# OBD-UART.net
KiCad netlist of a schematic drawn in EAGLE
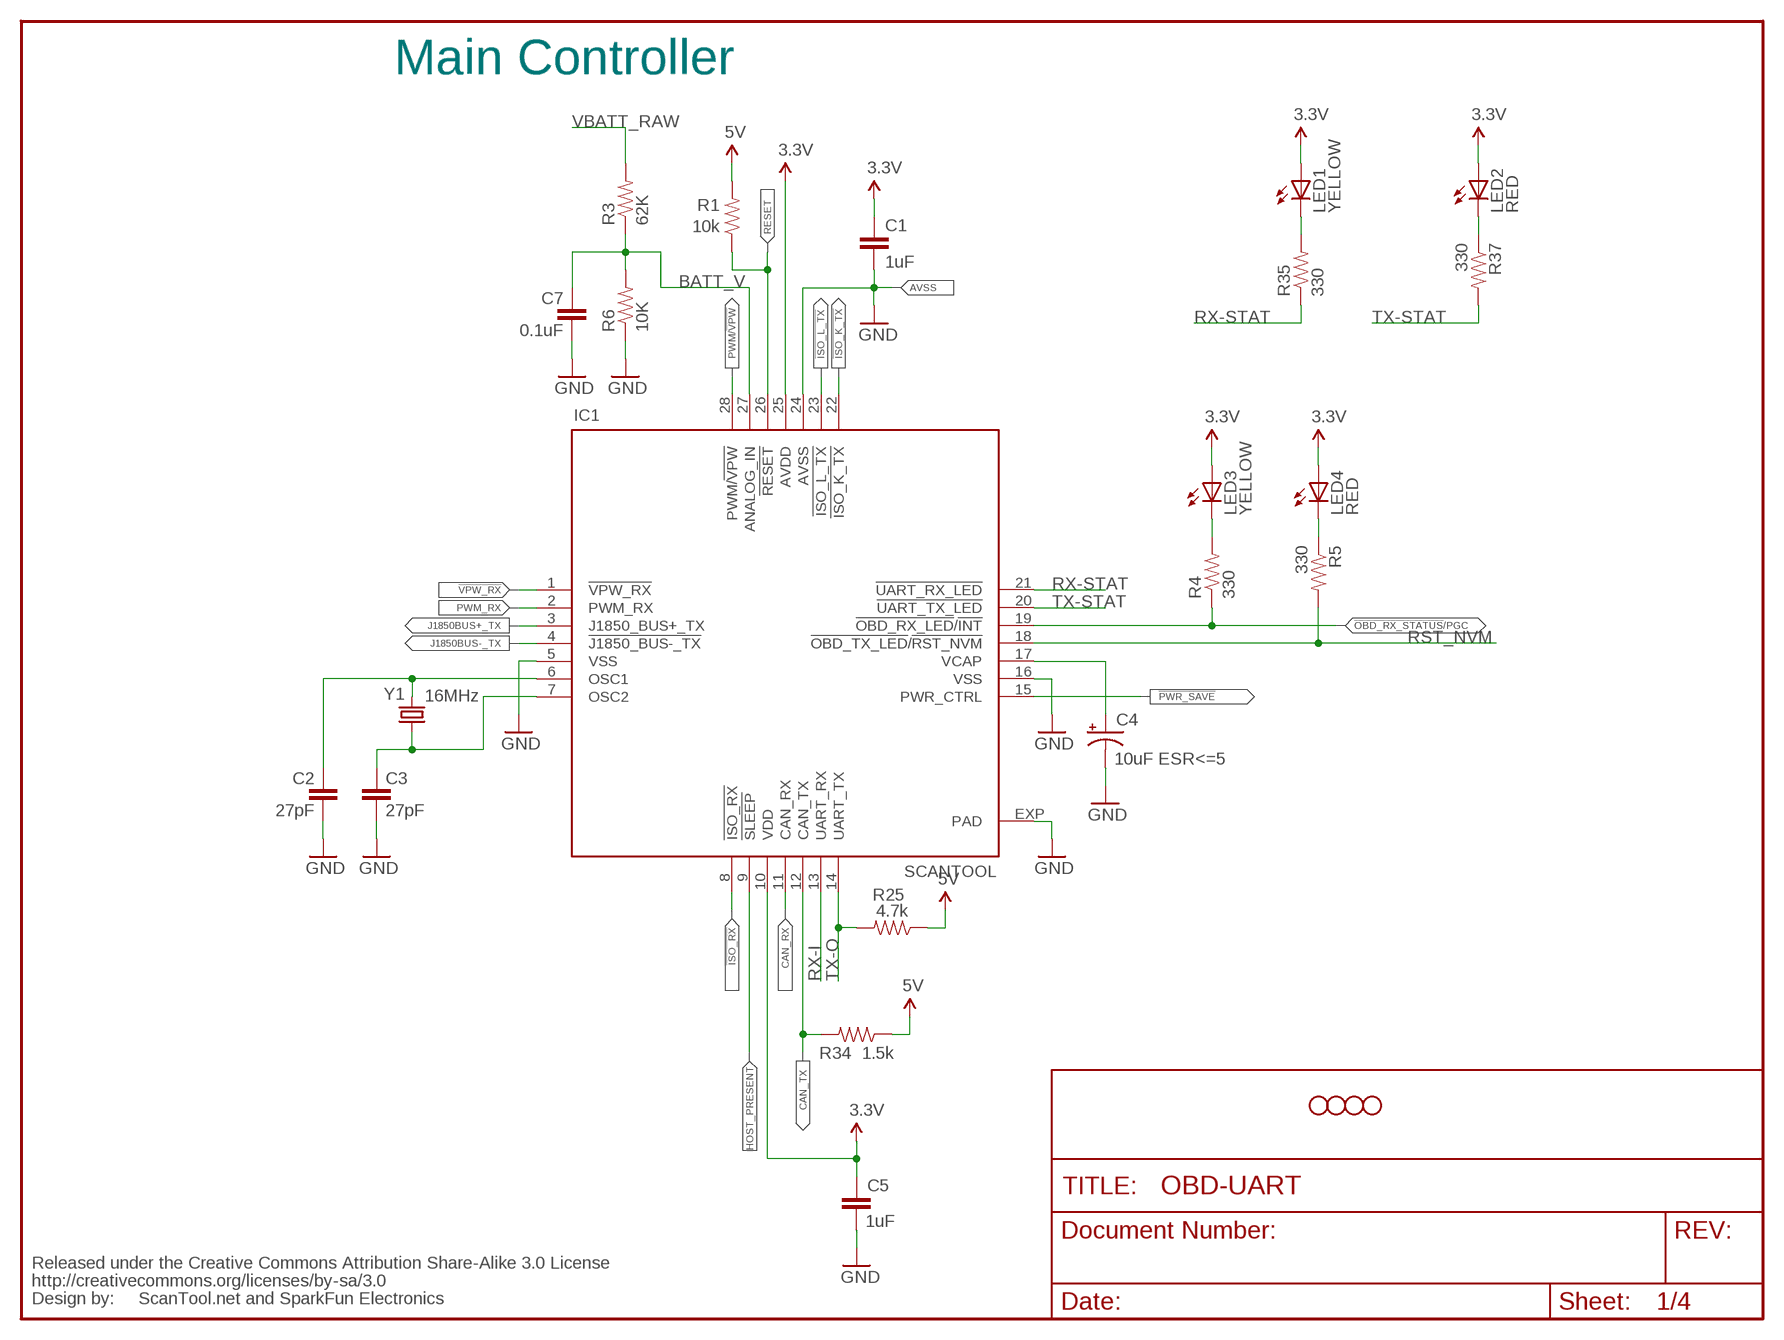
[diagram p0: schematic, sheet 1]
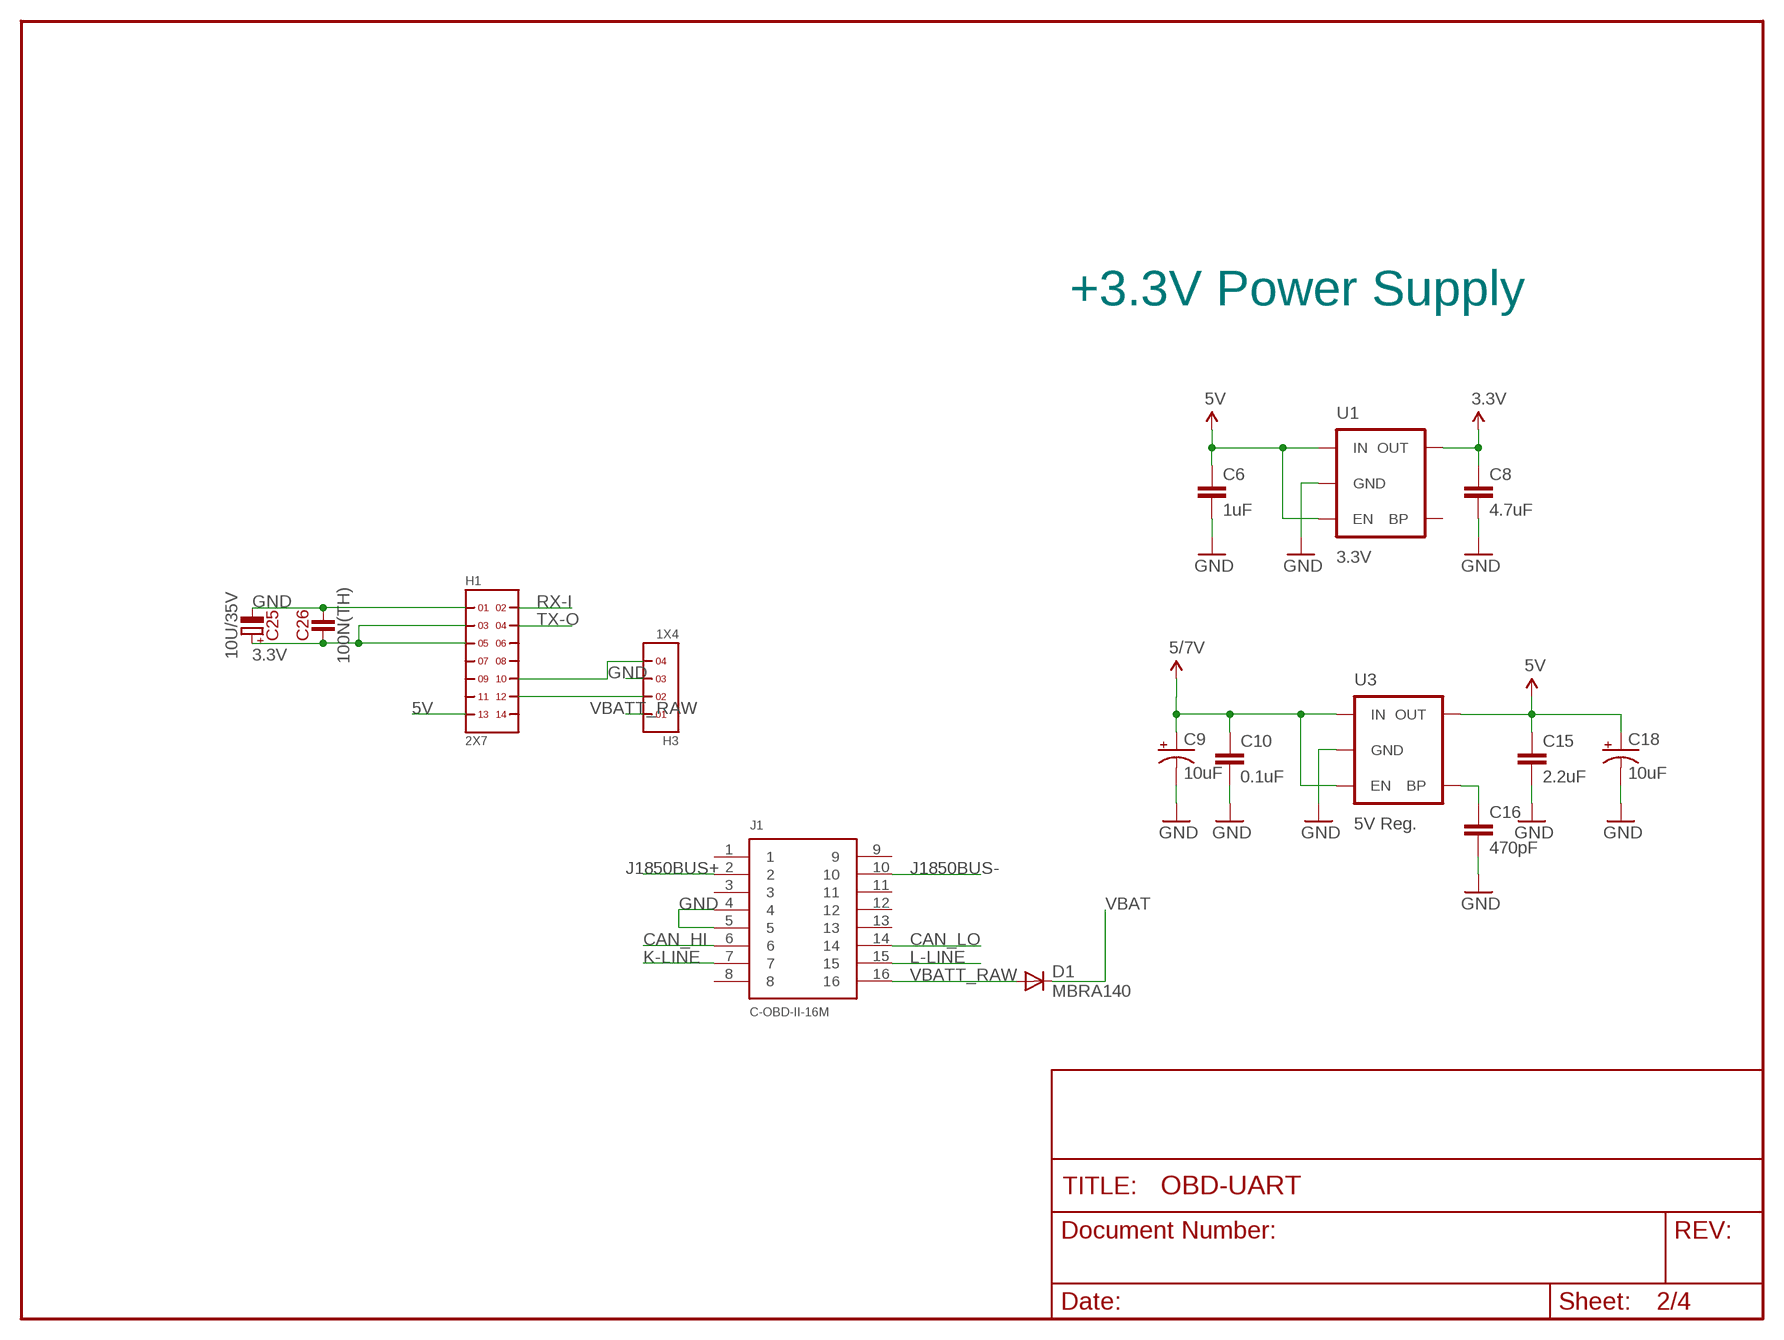
[diagram p1: schematic, sheet 2]
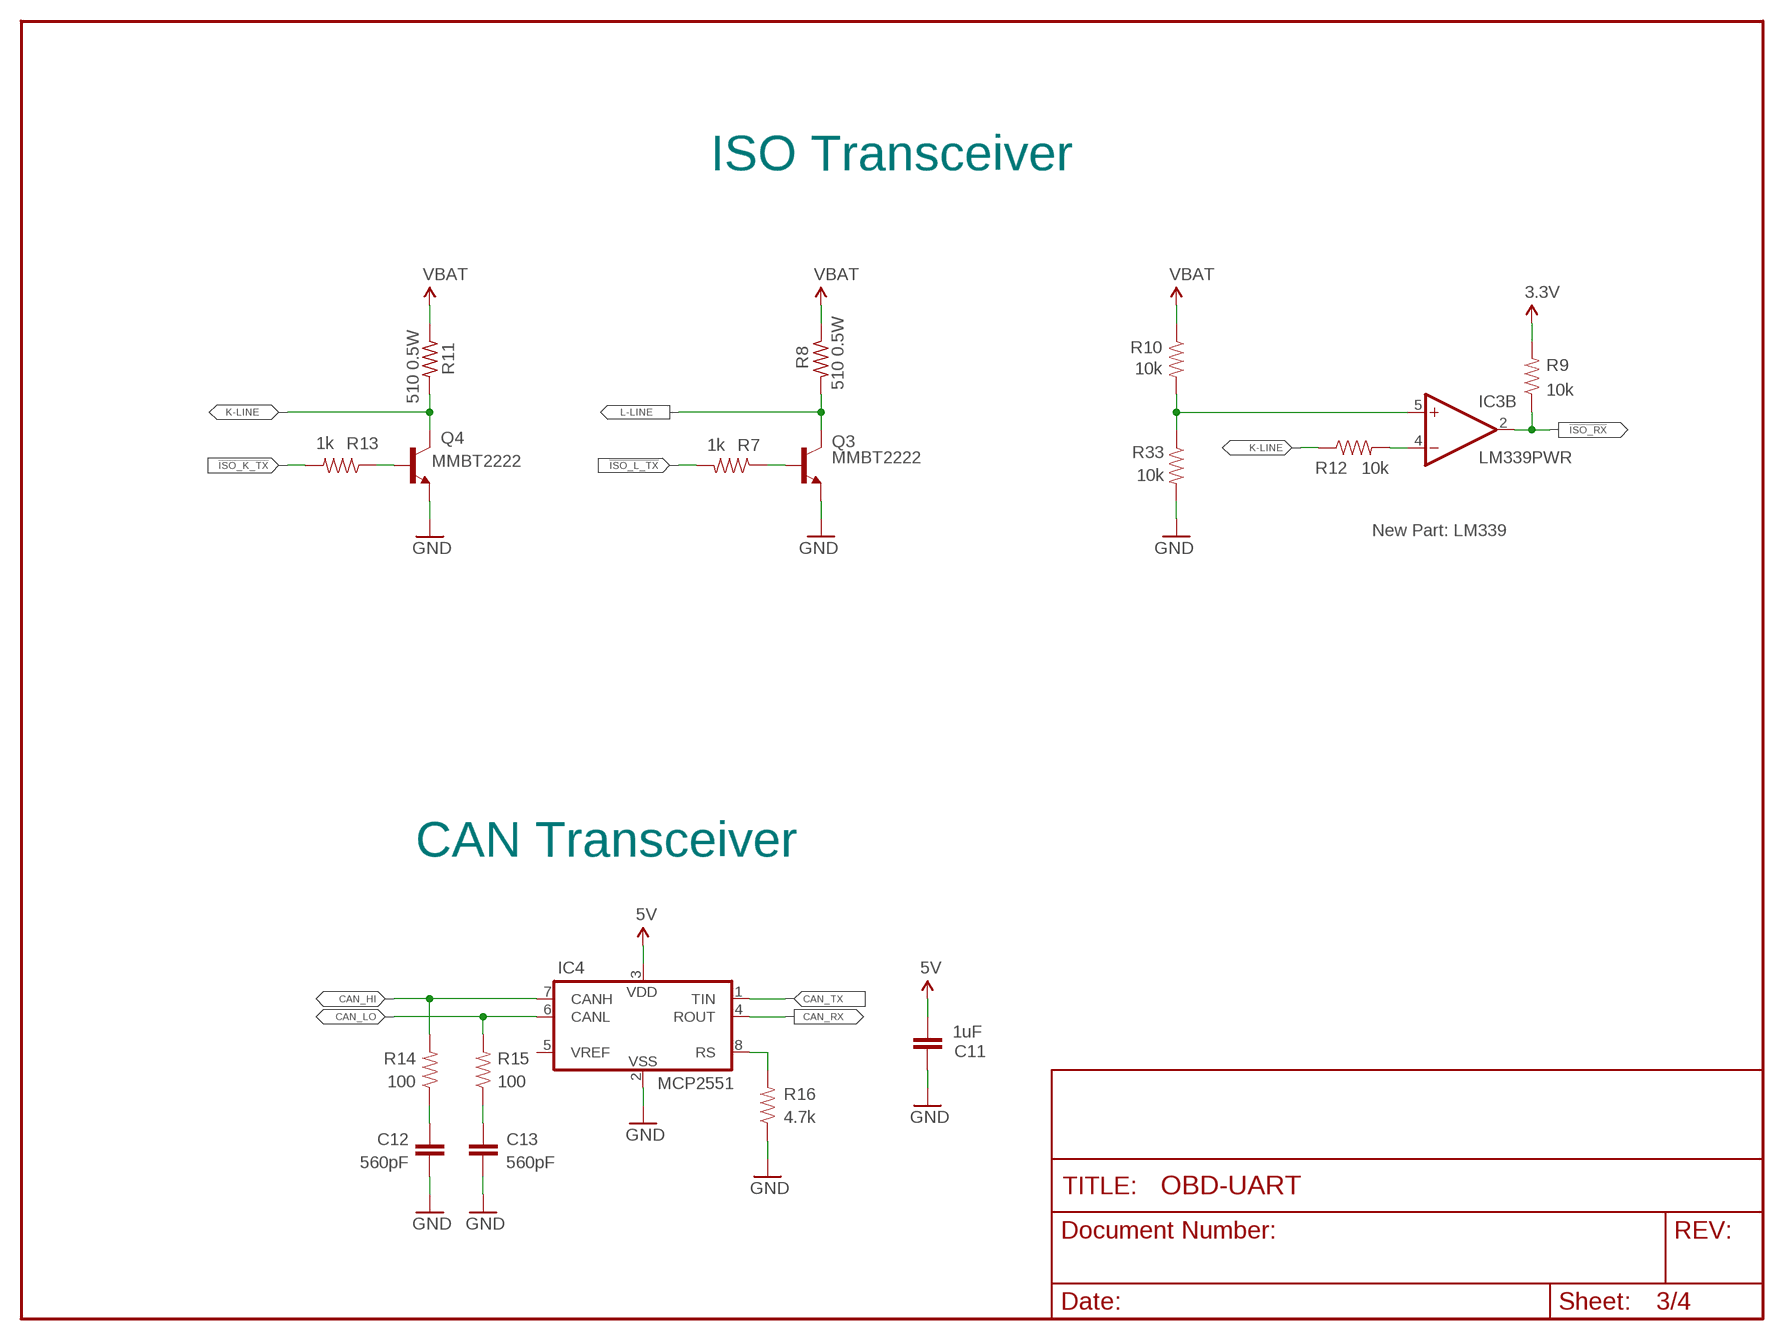
[diagram p2: schematic, sheet 3]
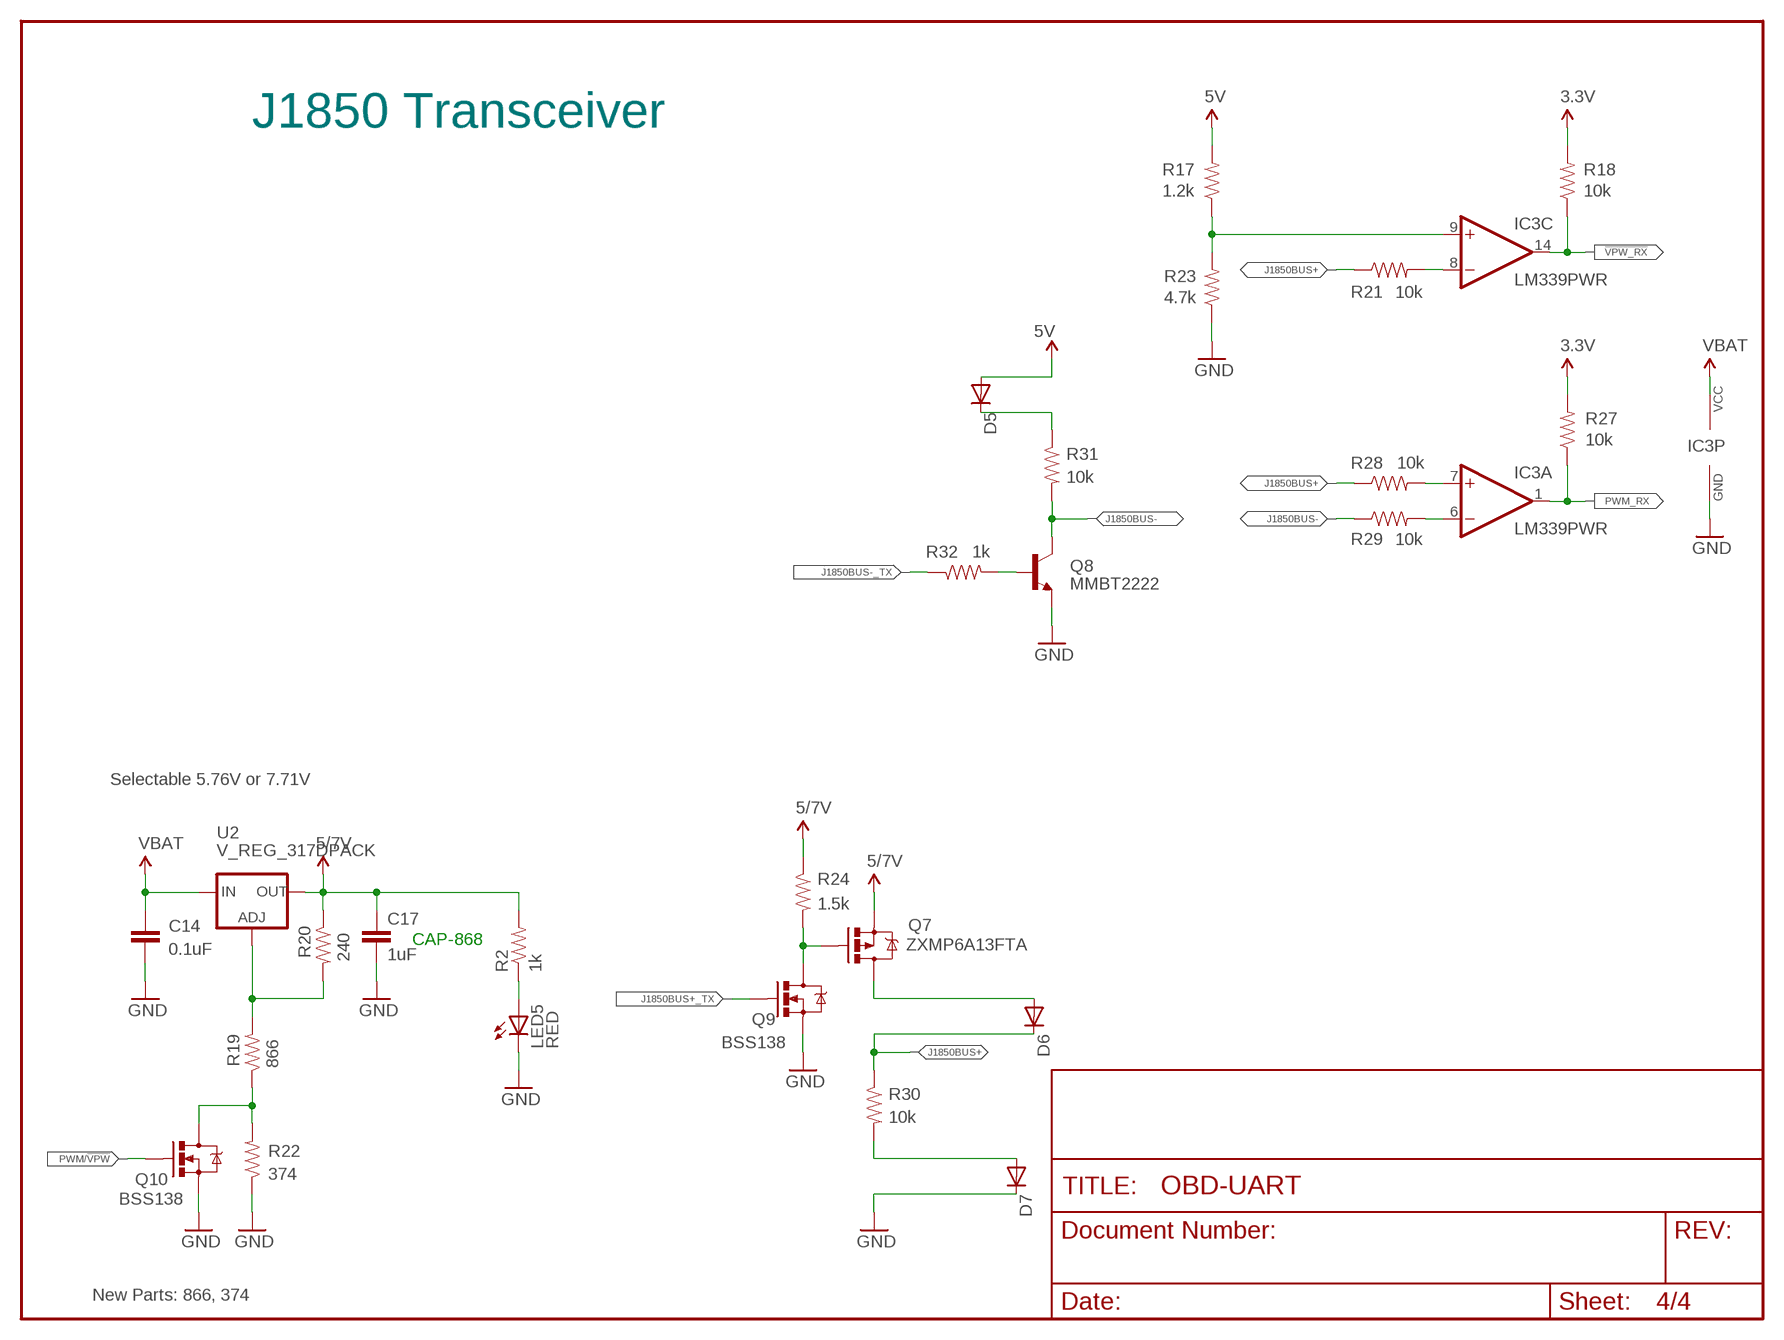
[diagram p3: schematic, sheet 4]

(export (version "E")
  (design (tool "Eeschema 10.0.6"))
  (components
    (comp (ref "C14")
      (value "0.1uF")
      (footprint "eagle-import:0402-CAP")
      (libsource (lib "eagle-import") (part "CAP0402-CAP"))
    )
    (comp (ref "C17")
      (value "1uF")
      (footprint "eagle-import:0402-CAP")
      (libsource (lib "eagle-import") (part "CAP0402-CAP"))
    )
    (comp (ref "D5")
      (value "DIODESOT23")
      (footprint "eagle-import:SOT23-3")
      (libsource (lib "eagle-import") (part "DIODESOT23"))
    )
    (comp (ref "D6")
      (value "DIODESOT23")
      (footprint "eagle-import:SOT23-3")
      (libsource (lib "eagle-import") (part "DIODESOT23"))
    )
    (comp (ref "D7")
      (value "DIODESOT23")
      (footprint "eagle-import:SOT23-3")
      (libsource (lib "eagle-import") (part "DIODESOT23"))
    )
    (comp (ref "IC3")
      (value "LM339PWR")
      (footprint "eagle-import:TSSOP-14")
      (libsource (lib "eagle-import") (part "LM339PWR"))
    )
    (comp (ref "LED5")
      (value "RED")
      (footprint "eagle-import:LED-0603")
      (libsource (lib "eagle-import") (part "LED0603"))
    )
    (comp (ref "Q7")
      (value "ZXMP6A13FTA")
      (footprint "eagle-import:SOT23")
      (libsource (lib "eagle-import") (part "MOSFET-PCHANNEL"))
    )
    (comp (ref "Q8")
      (value "MMBT2222")
      (footprint "eagle-import:SOT23-3")
      (libsource (lib "eagle-import") (part "TRANSISTOR_NPNSOT23-3"))
    )
    (comp (ref "Q9")
      (value "BSS138")
      (footprint "eagle-import:SOT23-3")
      (libsource (lib "eagle-import") (part "MOSFET-NCHANNELSMD"))
    )
    (comp (ref "Q10")
      (value "BSS138")
      (footprint "eagle-import:SOT23-3")
      (libsource (lib "eagle-import") (part "MOSFET-NCHANNELSMD"))
    )
    (comp (ref "R2")
      (value "1k")
      (footprint "eagle-import:0402-RES")
      (libsource (lib "eagle-import") (part "RESISTOR0402-RES"))
    )
    (comp (ref "R17")
      (value "1.2k")
      (footprint "eagle-import:0402-RES")
      (libsource (lib "eagle-import") (part "RESISTOR0402-RES"))
    )
    (comp (ref "R18")
      (value "10k")
      (footprint "eagle-import:0402-RES")
      (libsource (lib "eagle-import") (part "RESISTOR0402-RES"))
    )
    (comp (ref "R19")
      (value "866")
      (footprint "eagle-import:0402-RES")
      (libsource (lib "eagle-import") (part "RESISTOR0402-RES"))
    )
    (comp (ref "R20")
      (value "240")
      (footprint "eagle-import:0402-RES")
      (libsource (lib "eagle-import") (part "RESISTOR0402-RES"))
    )
    (comp (ref "R21")
      (value "10k")
      (footprint "eagle-import:0402-RES")
      (libsource (lib "eagle-import") (part "RESISTOR0402-RES"))
    )
    (comp (ref "R22")
      (value "374")
      (footprint "eagle-import:0402-RES")
      (libsource (lib "eagle-import") (part "RESISTOR0402-RES"))
    )
    (comp (ref "R23")
      (value "4.7k")
      (footprint "eagle-import:0402-RES")
      (libsource (lib "eagle-import") (part "RESISTOR0402-RES"))
    )
    (comp (ref "R24")
      (value "1.5k")
      (footprint "eagle-import:0402-RES")
      (libsource (lib "eagle-import") (part "RESISTOR0402-RES"))
    )
    (comp (ref "R27")
      (value "10k")
      (footprint "eagle-import:0402-RES")
      (libsource (lib "eagle-import") (part "RESISTOR0402-RES"))
    )
    (comp (ref "R28")
      (value "10k")
      (footprint "eagle-import:0402-RES")
      (libsource (lib "eagle-import") (part "RESISTOR0402-RES"))
    )
    (comp (ref "R29")
      (value "10k")
      (footprint "eagle-import:0402-RES")
      (libsource (lib "eagle-import") (part "RESISTOR0402-RES"))
    )
    (comp (ref "R30")
      (value "10k")
      (footprint "eagle-import:0402-RES")
      (libsource (lib "eagle-import") (part "RESISTOR0402-RES"))
    )
    (comp (ref "R31")
      (value "10k")
      (footprint "eagle-import:0402-RES")
      (libsource (lib "eagle-import") (part "RESISTOR0402-RES"))
    )
    (comp (ref "R32")
      (value "1k")
      (footprint "eagle-import:0402-RES")
      (libsource (lib "eagle-import") (part "RESISTOR0402-RES"))
    )
    (comp (ref "U2")
      (value "V_REG_317DPACK")
      (footprint "eagle-import:V-REG_DPACK")
      (libsource (lib "eagle-import") (part "V_REG_317DPACK"))
    )
    (comp (ref "C1")
      (value "1uF")
      (footprint "eagle-import:0402-CAP")
      (libsource (lib "eagle-import") (part "CAP0402-CAP"))
    )
    (comp (ref "C2")
      (value "27pF")
      (footprint "eagle-import:0402-CAP")
      (libsource (lib "eagle-import") (part "CAP0402-CAP"))
    )
    (comp (ref "C3")
      (value "27pF")
      (footprint "eagle-import:0402-CAP")
      (libsource (lib "eagle-import") (part "CAP0402-CAP"))
    )
    (comp (ref "C4")
      (value "10uF ESR<=5")
      (footprint "eagle-import:EIA3216")
      (libsource (lib "eagle-import") (part "CAP_POL1206"))
    )
    (comp (ref "C5")
      (value "1uF")
      (footprint "eagle-import:0402-CAP")
      (libsource (lib "eagle-import") (part "CAP0402-CAP"))
    )
    (comp (ref "C7")
      (value "0.1uF")
      (footprint "eagle-import:0402-CAP")
      (libsource (lib "eagle-import") (part "CAP0402-CAP"))
    )
    (comp (ref "IC1")
      (value "SCANTOOL")
      (footprint "eagle-import:_STN_SCANTOOL_QFN-28-S")
      (libsource (lib "eagle-import") (part "SCANTOOL"))
    )
    (comp (ref "JP4")
      (value "STAND-OFF")
      (footprint "eagle-import:STAND-OFF")
      (libsource (lib "eagle-import") (part "STAND-OFF"))
    )
    (comp (ref "JP5")
      (value "STAND-OFF")
      (footprint "eagle-import:STAND-OFF")
      (libsource (lib "eagle-import") (part "STAND-OFF"))
    )
    (comp (ref "JP6")
      (value "STAND-OFF")
      (footprint "eagle-import:STAND-OFF")
      (libsource (lib "eagle-import") (part "STAND-OFF"))
    )
    (comp (ref "JP7")
      (value "STAND-OFF")
      (footprint "eagle-import:STAND-OFF")
      (libsource (lib "eagle-import") (part "STAND-OFF"))
    )
    (comp (ref "LED1")
      (value "YELLOW")
      (footprint "eagle-import:LED-0603")
      (libsource (lib "eagle-import") (part "LED0603"))
    )
    (comp (ref "LED2")
      (value "RED")
      (footprint "eagle-import:LED-0603")
      (libsource (lib "eagle-import") (part "LED0603"))
    )
    (comp (ref "LED3")
      (value "YELLOW")
      (footprint "eagle-import:LED-0603")
      (libsource (lib "eagle-import") (part "LED0603"))
    )
    (comp (ref "LED4")
      (value "RED")
      (footprint "eagle-import:LED-0603")
      (libsource (lib "eagle-import") (part "LED0603"))
    )
    (comp (ref "R1")
      (value "10k")
      (footprint "eagle-import:0402-RES")
      (libsource (lib "eagle-import") (part "RESISTOR0402-RES"))
    )
    (comp (ref "R3")
      (value "62K")
      (footprint "eagle-import:0402-RES")
      (libsource (lib "eagle-import") (part "RESISTOR0402-RES"))
    )
    (comp (ref "R4")
      (value "330")
      (footprint "eagle-import:0402-RES")
      (libsource (lib "eagle-import") (part "RESISTOR0402-RES"))
    )
    (comp (ref "R5")
      (value "330")
      (footprint "eagle-import:0402-RES")
      (libsource (lib "eagle-import") (part "RESISTOR0402-RES"))
    )
    (comp (ref "R6")
      (value "10K")
      (footprint "eagle-import:0402-RES")
      (libsource (lib "eagle-import") (part "RESISTOR0402-RES"))
    )
    (comp (ref "R25")
      (value "4.7k")
      (footprint "eagle-import:0402-RES")
      (libsource (lib "eagle-import") (part "RESISTOR0402-RES"))
    )
    (comp (ref "R34")
      (value "1.5k")
      (footprint "eagle-import:0402-RES")
      (libsource (lib "eagle-import") (part "RESISTOR0402-RES"))
    )
    (comp (ref "R35")
      (value "330")
      (footprint "eagle-import:0402-RES")
      (libsource (lib "eagle-import") (part "RESISTOR0402-RES"))
    )
    (comp (ref "R37")
      (value "330")
      (footprint "eagle-import:0402-RES")
      (libsource (lib "eagle-import") (part "RESISTOR0402-RES"))
    )
    (comp (ref "U$1")
      (value "CREATIVE_COMMONS")
      (footprint "eagle-import:CREATIVE_COMMONS")
      (libsource (lib "eagle-import") (part "CREATIVE_COMMONS"))
    )
    (comp (ref "Y1")
      (value "16MHz")
      (footprint "eagle-import:CRYSTAL-SMD-5X3")
      (libsource (lib "eagle-import") (part "CRYSTAL5X3"))
    )
    (comp (ref "C11")
      (value "1uF")
      (footprint "eagle-import:0402-CAP")
      (libsource (lib "eagle-import") (part "CAP0402-CAP"))
    )
    (comp (ref "C12")
      (value "560pF")
      (footprint "eagle-import:0402-CAP")
      (libsource (lib "eagle-import") (part "CAP0402-CAP"))
    )
    (comp (ref "C13")
      (value "560pF")
      (footprint "eagle-import:0402-CAP")
      (libsource (lib "eagle-import") (part "CAP0402-CAP"))
    )
    (comp (ref "IC4")
      (value "MCP2551")
      (footprint "eagle-import:SO-8")
      (fields (field (name "PARTNUM") "MCP2551-I/SN"))
      (libsource (lib "eagle-import") (part "MCP2551-I/SN"))
    )
    (comp (ref "Q3")
      (value "MMBT2222")
      (footprint "eagle-import:SOT23-3")
      (libsource (lib "eagle-import") (part "TRANSISTOR_NPNSOT23-3"))
    )
    (comp (ref "Q4")
      (value "MMBT2222")
      (footprint "eagle-import:SOT23-3")
      (libsource (lib "eagle-import") (part "TRANSISTOR_NPNSOT23-3"))
    )
    (comp (ref "R7")
      (value "1k")
      (footprint "eagle-import:0402-RES")
      (libsource (lib "eagle-import") (part "RESISTOR0402-RES"))
    )
    (comp (ref "R8")
      (value "510 0.5W")
      (footprint "eagle-import:2010")
      (libsource (lib "eagle-import") (part "R-US_2010"))
    )
    (comp (ref "R9")
      (value "10k")
      (footprint "eagle-import:0402-RES")
      (libsource (lib "eagle-import") (part "RESISTOR0402-RES"))
    )
    (comp (ref "R10")
      (value "10k")
      (footprint "eagle-import:0402-RES")
      (libsource (lib "eagle-import") (part "RESISTOR0402-RES"))
    )
    (comp (ref "R11")
      (value "510 0.5W")
      (footprint "eagle-import:2010")
      (libsource (lib "eagle-import") (part "R-US_2010"))
    )
    (comp (ref "R12")
      (value "10k")
      (footprint "eagle-import:0402-RES")
      (libsource (lib "eagle-import") (part "RESISTOR0402-RES"))
    )
    (comp (ref "R13")
      (value "1k")
      (footprint "eagle-import:0402-RES")
      (libsource (lib "eagle-import") (part "RESISTOR0402-RES"))
    )
    (comp (ref "R14")
      (value "100")
      (footprint "eagle-import:0402-RES")
      (libsource (lib "eagle-import") (part "RESISTOR0402-RES"))
    )
    (comp (ref "R15")
      (value "100")
      (footprint "eagle-import:0402-RES")
      (libsource (lib "eagle-import") (part "RESISTOR0402-RES"))
    )
    (comp (ref "R16")
      (value "4.7k")
      (footprint "eagle-import:0402-RES")
      (libsource (lib "eagle-import") (part "RESISTOR0402-RES"))
    )
    (comp (ref "R33")
      (value "10k")
      (footprint "eagle-import:0402-RES")
      (libsource (lib "eagle-import") (part "RESISTOR0402-RES"))
    )
    (comp (ref "C6")
      (value "1uF")
      (footprint "eagle-import:0402-CAP")
      (libsource (lib "eagle-import") (part "CAP0402-CAP"))
    )
    (comp (ref "C8")
      (value "4.7uF")
      (footprint "eagle-import:0402-CAP")
      (libsource (lib "eagle-import") (part "CAP0402-CAP"))
    )
    (comp (ref "C9")
      (value "10uF")
      (footprint "eagle-import:EIA3216")
      (libsource (lib "eagle-import") (part "CAP_POL1206"))
    )
    (comp (ref "C10")
      (value "0.1uF")
      (footprint "eagle-import:0402-CAP")
      (libsource (lib "eagle-import") (part "CAP0402-CAP"))
    )
    (comp (ref "C15")
      (value "2.2uF")
      (footprint "eagle-import:0402-CAP")
      (libsource (lib "eagle-import") (part "CAP0402-CAP"))
    )
    (comp (ref "C16")
      (value "470pF")
      (footprint "eagle-import:0402-CAP")
      (libsource (lib "eagle-import") (part "CAP0402-CAP"))
    )
    (comp (ref "C18")
      (value "10uF")
      (footprint "eagle-import:EIA3216")
      (libsource (lib "eagle-import") (part "CAP_POL1206"))
    )
    (comp (ref "C25")
      (value "10U/35V")
      (footprint "eagle-import:E2-5")
      (libsource (lib "eagle-import") (part "?10U/35V"))
    )
    (comp (ref "C26")
      (value "100N(TH)")
      (footprint "eagle-import:C050-024X044")
      (libsource (lib "eagle-import") (part "?100N(TH)"))
    )
    (comp (ref "D1")
      (value "MBRA140")
      (footprint "eagle-import:SMA-DIODE")
      (libsource (lib "eagle-import") (part "DIODESMA"))
    )
    (comp (ref "H1")
      (value "2X7")
      (footprint "eagle-import:2X7")
      (libsource (lib "eagle-import") (part "2X7"))
    )
    (comp (ref "H3")
      (value "1X4")
      (footprint "eagle-import:1X4")
      (libsource (lib "eagle-import") (part "1X4"))
    )
    (comp (ref "J1")
      (value "C-OBD-II-16M")
      (footprint "eagle-import:COMTECH_C-OBD-II-16M")
      (fields (field (name "MF") "Comtech Electronic Co., LTD"))
      (libsource (lib "eagle-import") (part "C-OBD-II-16M"))
    )
    (comp (ref "U1")
      (value "3.3V")
      (footprint "eagle-import:SOT23-5")
      (libsource (lib "eagle-import") (part "V_REG_LDOSMD"))
    )
    (comp (ref "U3")
      (value "5V Reg.")
      (footprint "eagle-import:SOT23-5")
      (libsource (lib "eagle-import") (part "V_REG_LDOSMD"))
    )
  )
  (nets
    (net (code "1") (name "3.3V") (class "Default")
      (node (ref "C1") (pin "1") (pinfunction "1_1") (pintype "passive"))
      (node (ref "C25") (pin "+") (pinfunction "+_+") (pintype "passive"))
      (node (ref "C26") (pin "1") (pinfunction "1_1") (pintype "passive"))
      (node (ref "C5") (pin "1") (pinfunction "1_1") (pintype "passive"))
      (node (ref "C8") (pin "1") (pinfunction "1_1") (pintype "passive"))
      (node (ref "H1") (pin "3") (pinfunction "3_3") (pintype "bidirectional"))
      (node (ref "H1") (pin "5") (pinfunction "5_5") (pintype "bidirectional"))
      (node (ref "IC1") (pin "10") (pinfunction "VDD_10") (pintype "power_in"))
      (node (ref "IC1") (pin "25") (pinfunction "AVDD_25") (pintype "power_in"))
      (node (ref "LED1") (pin "A") (pinfunction "A_A") (pintype "passive"))
      (node (ref "LED2") (pin "A") (pinfunction "A_A") (pintype "passive"))
      (node (ref "LED3") (pin "A") (pinfunction "A_A") (pintype "passive"))
      (node (ref "LED4") (pin "A") (pinfunction "A_A") (pintype "passive"))
      (node (ref "R18") (pin "2") (pinfunction "2_2") (pintype "passive"))
      (node (ref "R27") (pin "2") (pinfunction "2_2") (pintype "passive"))
      (node (ref "R9") (pin "2") (pinfunction "2_2") (pintype "passive"))
      (node (ref "U1") (pin "5") (pinfunction "OUT_5") (pintype "passive"))
    )
    (net (code "2") (name "5V") (class "Default")
      (node (ref "C11") (pin "1") (pinfunction "1_1") (pintype "passive"))
      (node (ref "C15") (pin "1") (pinfunction "1_1") (pintype "passive"))
      (node (ref "C18") (pin "A") (pinfunction "+_A") (pintype "passive"))
      (node (ref "C6") (pin "1") (pinfunction "1_1") (pintype "passive"))
      (node (ref "D5") (pin "1") (pinfunction "A_1") (pintype "passive"))
      (node (ref "H1") (pin "13") (pinfunction "13_13") (pintype "bidirectional"))
      (node (ref "IC4") (pin "3") (pinfunction "VDD_3") (pintype "power_in"))
      (node (ref "R1") (pin "2") (pinfunction "2_2") (pintype "passive"))
      (node (ref "R17") (pin "2") (pinfunction "2_2") (pintype "passive"))
      (node (ref "R25") (pin "1") (pinfunction "1_1") (pintype "passive"))
      (node (ref "R34") (pin "1") (pinfunction "1_1") (pintype "passive"))
      (node (ref "U1") (pin "1") (pinfunction "IN_1") (pintype "input"))
      (node (ref "U1") (pin "3") (pinfunction "EN_3") (pintype "input"))
      (node (ref "U3") (pin "5") (pinfunction "OUT_5") (pintype "passive"))
    )
    (net (code "3") (name "BATT_V") (class "Default")
      (node (ref "C7") (pin "1") (pinfunction "1_1") (pintype "passive"))
      (node (ref "IC1") (pin "27") (pinfunction "ANALOG_IN_27") (pintype "input"))
      (node (ref "R3") (pin "1") (pinfunction "1_1") (pintype "passive"))
      (node (ref "R6") (pin "2") (pinfunction "2_2") (pintype "passive"))
    )
    (net (code "4") (name "CAN_HI") (class "Default")
      (node (ref "IC4") (pin "7") (pinfunction "CANH_7") (pintype "bidirectional"))
      (node (ref "J1") (pin "6") (pinfunction "6_6") (pintype "passive"))
      (node (ref "R14") (pin "2") (pinfunction "2_2") (pintype "passive"))
    )
    (net (code "5") (name "CAN_LO") (class "Default")
      (node (ref "IC4") (pin "6") (pinfunction "CANL_6") (pintype "bidirectional"))
      (node (ref "J1") (pin "14") (pinfunction "14_14") (pintype "passive"))
      (node (ref "R15") (pin "2") (pinfunction "2_2") (pintype "passive"))
    )
    (net (code "6") (name "CAN_RX") (class "Default")
      (node (ref "IC1") (pin "11") (pinfunction "CAN_RX_11") (pintype "input"))
      (node (ref "IC4") (pin "4") (pinfunction "ROUT_4") (pintype "output"))
    )
    (net (code "7") (name "CAN_TX") (class "Default")
      (node (ref "IC1") (pin "12") (pinfunction "CAN_TX_12") (pintype "output"))
      (node (ref "IC4") (pin "1") (pinfunction "TIN_1") (pintype "input"))
      (node (ref "R34") (pin "2") (pinfunction "2_2") (pintype "passive"))
    )
    (net (code "8") (name "GND") (class "Default")
      (node (ref "C1") (pin "2") (pinfunction "2_2") (pintype "passive"))
      (node (ref "C10") (pin "2") (pinfunction "2_2") (pintype "passive"))
      (node (ref "C11") (pin "2") (pinfunction "2_2") (pintype "passive"))
      (node (ref "C12") (pin "2") (pinfunction "2_2") (pintype "passive"))
      (node (ref "C13") (pin "2") (pinfunction "2_2") (pintype "passive"))
      (node (ref "C14") (pin "2") (pinfunction "2_2") (pintype "passive"))
      (node (ref "C15") (pin "2") (pinfunction "2_2") (pintype "passive"))
      (node (ref "C16") (pin "2") (pinfunction "2_2") (pintype "passive"))
      (node (ref "C17") (pin "2") (pinfunction "2_2") (pintype "passive"))
      (node (ref "C18") (pin "C") (pinfunction "-_C") (pintype "passive"))
      (node (ref "C2") (pin "2") (pinfunction "2_2") (pintype "passive"))
      (node (ref "C25") (pin "-") (pinfunction "-_-") (pintype "passive"))
      (node (ref "C26") (pin "2") (pinfunction "2_2") (pintype "passive"))
      (node (ref "C3") (pin "2") (pinfunction "2_2") (pintype "passive"))
      (node (ref "C4") (pin "C") (pinfunction "-_C") (pintype "passive"))
      (node (ref "C5") (pin "2") (pinfunction "2_2") (pintype "passive"))
      (node (ref "C6") (pin "2") (pinfunction "2_2") (pintype "passive"))
      (node (ref "C7") (pin "2") (pinfunction "2_2") (pintype "passive"))
      (node (ref "C8") (pin "2") (pinfunction "2_2") (pintype "passive"))
      (node (ref "C9") (pin "C") (pinfunction "-_C") (pintype "passive"))
      (node (ref "D7") (pin "3") (pinfunction "C_3") (pintype "passive"))
      (node (ref "H1") (pin "1") (pinfunction "1_1") (pintype "bidirectional"))
      (node (ref "H3") (pin "3") (pinfunction "3_3") (pintype "bidirectional"))
      (node (ref "IC1") (pin "16") (pinfunction "VSS_16") (pintype "power_in"))
      (node (ref "IC1") (pin "24") (pinfunction "AVSS_24") (pintype "power_in"))
      (node (ref "IC1") (pin "5") (pinfunction "VSS_5") (pintype "power_in"))
      (node (ref "IC1") (pin "EXP") (pinfunction "PAD_EXP") (pintype "passive"))
      (node (ref "IC3") (pin "12") (pinfunction "GND_12") (pintype "power_in"))
      (node (ref "IC4") (pin "2") (pinfunction "VSS_2") (pintype "power_in"))
      (node (ref "J1") (pin "4") (pinfunction "4_4") (pintype "passive"))
      (node (ref "J1") (pin "5") (pinfunction "5_5") (pintype "passive"))
      (node (ref "LED5") (pin "C") (pinfunction "C_C") (pintype "passive"))
      (node (ref "Q10") (pin "2") (pinfunction "S_2") (pintype "passive"))
      (node (ref "Q3") (pin "2") (pinfunction "E_2") (pintype "passive"))
      (node (ref "Q4") (pin "2") (pinfunction "E_2") (pintype "passive"))
      (node (ref "Q8") (pin "2") (pinfunction "E_2") (pintype "passive"))
      (node (ref "Q9") (pin "2") (pinfunction "S_2") (pintype "passive"))
      (node (ref "R16") (pin "1") (pinfunction "1_1") (pintype "passive"))
      (node (ref "R22") (pin "1") (pinfunction "1_1") (pintype "passive"))
      (node (ref "R23") (pin "1") (pinfunction "1_1") (pintype "passive"))
      (node (ref "R33") (pin "2") (pinfunction "2_2") (pintype "passive"))
      (node (ref "R6") (pin "1") (pinfunction "1_1") (pintype "passive"))
      (node (ref "U1") (pin "2") (pinfunction "GND_2") (pintype "input"))
      (node (ref "U3") (pin "2") (pinfunction "GND_2") (pintype "input"))
    )
    (net (code "9") (name "HOST_PRESENT") (class "Default")
      (node (ref "IC1") (pin "9") (pinfunction "~{SLEEP}_9") (pintype "input"))
    )
    (net (code "10") (name "J1850BUS+") (class "Default")
      (node (ref "D6") (pin "3") (pinfunction "C_3") (pintype "passive"))
      (node (ref "J1") (pin "2") (pinfunction "2_2") (pintype "passive"))
      (node (ref "R21") (pin "1") (pinfunction "1_1") (pintype "passive"))
      (node (ref "R28") (pin "1") (pinfunction "1_1") (pintype "passive"))
      (node (ref "R30") (pin "1") (pinfunction "1_1") (pintype "passive"))
    )
    (net (code "11") (name "J1850BUS+_TX") (class "Default")
      (node (ref "IC1") (pin "3") (pinfunction "J1850_BUS+_TX_3") (pintype "output"))
      (node (ref "Q9") (pin "1") (pinfunction "G_1") (pintype "passive"))
    )
    (net (code "12") (name "J1850BUS-") (class "Default")
      (node (ref "J1") (pin "10") (pinfunction "10_10") (pintype "passive"))
      (node (ref "Q8") (pin "3") (pinfunction "C_3") (pintype "passive"))
      (node (ref "R29") (pin "1") (pinfunction "1_1") (pintype "passive"))
      (node (ref "R31") (pin "2") (pinfunction "2_2") (pintype "passive"))
    )
    (net (code "13") (name "J1850BUS-_TX") (class "Default")
      (node (ref "IC1") (pin "4") (pinfunction "~{J1850_BUS-_TX}_4") (pintype "output"))
      (node (ref "R32") (pin "1") (pinfunction "1_1") (pintype "passive"))
    )
    (net (code "14") (name "K-LINE") (class "Default")
      (node (ref "J1") (pin "7") (pinfunction "7_7") (pintype "passive"))
      (node (ref "Q4") (pin "3") (pinfunction "C_3") (pintype "passive"))
      (node (ref "R11") (pin "2") (pinfunction "2_2") (pintype "passive"))
      (node (ref "R12") (pin "1") (pinfunction "1_1") (pintype "passive"))
    )
    (net (code "15") (name "L-LINE") (class "Default")
      (node (ref "J1") (pin "15") (pinfunction "15_15") (pintype "passive"))
      (node (ref "Q3") (pin "3") (pinfunction "C_3") (pintype "passive"))
      (node (ref "R8") (pin "2") (pinfunction "2_2") (pintype "passive"))
    )
    (net (code "16") (name "Net-(C4-+)") (class "Default")
      (node (ref "C4") (pin "A") (pinfunction "+_A") (pintype "passive"))
      (node (ref "IC1") (pin "17") (pinfunction "VCAP_17") (pintype "power_in"))
    )
    (net (code "17") (name "Net-(C12-Pad1)") (class "Default")
      (node (ref "C12") (pin "1") (pinfunction "1_1") (pintype "passive"))
      (node (ref "R14") (pin "1") (pinfunction "1_1") (pintype "passive"))
    )
    (net (code "18") (name "Net-(C13-Pad1)") (class "Default")
      (node (ref "C13") (pin "1") (pinfunction "1_1") (pintype "passive"))
      (node (ref "R15") (pin "1") (pinfunction "1_1") (pintype "passive"))
    )
    (net (code "19") (name "Net-(D5-C)") (class "Default")
      (node (ref "D5") (pin "3") (pinfunction "C_3") (pintype "passive"))
      (node (ref "R31") (pin "1") (pinfunction "1_1") (pintype "passive"))
    )
    (net (code "20") (name "Net-(D6-A)") (class "Default")
      (node (ref "D6") (pin "1") (pinfunction "A_1") (pintype "passive"))
      (node (ref "Q7") (pin "3") (pinfunction "D_3") (pintype "passive"))
    )
    (net (code "21") (name "Net-(D7-A)") (class "Default")
      (node (ref "D7") (pin "1") (pinfunction "A_1") (pintype "passive"))
      (node (ref "R30") (pin "2") (pinfunction "2_2") (pintype "passive"))
    )
    (net (code "22") (name "Net-(H1-Pad10)") (class "Default")
      (node (ref "H1") (pin "10") (pinfunction "10_10") (pintype "bidirectional"))
      (node (ref "H3") (pin "4") (pinfunction "4_4") (pintype "bidirectional"))
    )
    (net (code "23") (name "Net-(H1-Pad12)") (class "Default")
      (node (ref "H1") (pin "12") (pinfunction "12_12") (pintype "bidirectional"))
      (node (ref "H3") (pin "2") (pinfunction "2_2") (pintype "bidirectional"))
    )
    (net (code "24") (name "Net-(IC1-OSC1)") (class "Default")
      (node (ref "C2") (pin "1") (pinfunction "1_1") (pintype "passive"))
      (node (ref "IC1") (pin "6") (pinfunction "OSC1_6") (pintype "input"))
      (node (ref "Y1") (pin "3") (pinfunction "2_3") (pintype "passive"))
    )
    (net (code "25") (name "Net-(IC1-OSC2)") (class "Default")
      (node (ref "C3") (pin "1") (pinfunction "1_1") (pintype "passive"))
      (node (ref "IC1") (pin "7") (pinfunction "OSC2_7") (pintype "output"))
      (node (ref "Y1") (pin "1") (pinfunction "1_1") (pintype "passive"))
    )
    (net (code "26") (name "Net-(IC3A-+IN)") (class "Default")
      (node (ref "IC3") (pin "7") (pinfunction "+IN_7") (pintype "input"))
      (node (ref "R28") (pin "2") (pinfunction "2_2") (pintype "passive"))
    )
    (net (code "27") (name "Net-(IC3A--IN)") (class "Default")
      (node (ref "IC3") (pin "6") (pinfunction "-IN_6") (pintype "input"))
      (node (ref "R29") (pin "2") (pinfunction "2_2") (pintype "passive"))
    )
    (net (code "28") (name "Net-(IC3B-+IN)") (class "Default")
      (node (ref "IC3") (pin "5") (pinfunction "+IN_5") (pintype "input"))
      (node (ref "R10") (pin "2") (pinfunction "2_2") (pintype "passive"))
      (node (ref "R33") (pin "1") (pinfunction "1_1") (pintype "passive"))
    )
    (net (code "29") (name "Net-(IC3B--IN)") (class "Default")
      (node (ref "IC3") (pin "4") (pinfunction "-IN_4") (pintype "input"))
      (node (ref "R12") (pin "2") (pinfunction "2_2") (pintype "passive"))
    )
    (net (code "30") (name "Net-(IC3C-+IN)") (class "Default")
      (node (ref "IC3") (pin "9") (pinfunction "+IN_9") (pintype "input"))
      (node (ref "R17") (pin "1") (pinfunction "1_1") (pintype "passive"))
      (node (ref "R23") (pin "2") (pinfunction "2_2") (pintype "passive"))
    )
    (net (code "31") (name "Net-(IC3C--IN)") (class "Default")
      (node (ref "IC3") (pin "8") (pinfunction "-IN_8") (pintype "input"))
      (node (ref "R21") (pin "2") (pinfunction "2_2") (pintype "passive"))
    )
    (net (code "32") (name "Net-(IC4-RS)") (class "Default")
      (node (ref "IC4") (pin "8") (pinfunction "RS_8") (pintype "input"))
      (node (ref "R16") (pin "2") (pinfunction "2_2") (pintype "passive"))
    )
    (net (code "33") (name "Net-(LED1-PadC)") (class "Default")
      (node (ref "LED1") (pin "C") (pinfunction "C_C") (pintype "passive"))
      (node (ref "R35") (pin "2") (pinfunction "2_2") (pintype "passive"))
    )
    (net (code "34") (name "Net-(LED2-PadC)") (class "Default")
      (node (ref "LED2") (pin "C") (pinfunction "C_C") (pintype "passive"))
      (node (ref "R37") (pin "1") (pinfunction "1_1") (pintype "passive"))
    )
    (net (code "35") (name "Net-(LED3-PadC)") (class "Default")
      (node (ref "LED3") (pin "C") (pinfunction "C_C") (pintype "passive"))
      (node (ref "R4") (pin "2") (pinfunction "2_2") (pintype "passive"))
    )
    (net (code "36") (name "Net-(LED4-PadC)") (class "Default")
      (node (ref "LED4") (pin "C") (pinfunction "C_C") (pintype "passive"))
      (node (ref "R5") (pin "1") (pinfunction "1_1") (pintype "passive"))
    )
    (net (code "37") (name "Net-(LED5-PadA)") (class "Default")
      (node (ref "LED5") (pin "A") (pinfunction "A_A") (pintype "passive"))
      (node (ref "R2") (pin "1") (pinfunction "1_1") (pintype "passive"))
    )
    (net (code "38") (name "Net-(Q3-B)") (class "Default")
      (node (ref "Q3") (pin "1") (pinfunction "B_1") (pintype "passive"))
      (node (ref "R7") (pin "1") (pinfunction "1_1") (pintype "passive"))
    )
    (net (code "39") (name "Net-(Q4-B)") (class "Default")
      (node (ref "Q4") (pin "1") (pinfunction "B_1") (pintype "passive"))
      (node (ref "R13") (pin "1") (pinfunction "1_1") (pintype "passive"))
    )
    (net (code "40") (name "Net-(Q7-G)") (class "Default")
      (node (ref "Q7") (pin "1") (pinfunction "G_1") (pintype "passive"))
      (node (ref "Q9") (pin "3") (pinfunction "D_3") (pintype "passive"))
      (node (ref "R24") (pin "2") (pinfunction "2_2") (pintype "passive"))
    )
    (net (code "41") (name "Net-(Q8-B)") (class "Default")
      (node (ref "Q8") (pin "1") (pinfunction "B_1") (pintype "passive"))
      (node (ref "R32") (pin "2") (pinfunction "2_2") (pintype "passive"))
    )
    (net (code "42") (name "Net-(Q10-D)") (class "Default")
      (node (ref "Q10") (pin "3") (pinfunction "D_3") (pintype "passive"))
      (node (ref "R19") (pin "1") (pinfunction "1_1") (pintype "passive"))
      (node (ref "R22") (pin "2") (pinfunction "2_2") (pintype "passive"))
    )
    (net (code "43") (name "Net-(U2-ADJ)") (class "Default")
      (node (ref "R19") (pin "2") (pinfunction "2_2") (pintype "passive"))
      (node (ref "R20") (pin "2") (pinfunction "2_2") (pintype "passive"))
      (node (ref "U2") (pin "1") (pinfunction "ADJ_1") (pintype "input"))
    )
    (net (code "44") (name "Net-(U3-BP)") (class "Default")
      (node (ref "C16") (pin "1") (pinfunction "1_1") (pintype "passive"))
      (node (ref "U3") (pin "4") (pinfunction "BP_4") (pintype "input"))
    )
    (net (code "45") (name "PWM_RX") (class "Default")
      (node (ref "IC1") (pin "2") (pinfunction "PWM_RX_2") (pintype "input"))
      (node (ref "IC3") (pin "1") (pinfunction "OUT_1") (pintype "output"))
      (node (ref "R27") (pin "1") (pinfunction "1_1") (pintype "passive"))
    )
    (net (code "46") (name "PWM{slash}~{VPW}") (class "Default")
      (node (ref "IC1") (pin "28") (pinfunction "PWM/~{VPW}_28") (pintype "output"))
      (node (ref "Q10") (pin "1") (pinfunction "G_1") (pintype "passive"))
    )
    (net (code "47") (name "RESET") (class "Default")
      (node (ref "IC1") (pin "26") (pinfunction "~{RESET}_26") (pintype "input"))
      (node (ref "R1") (pin "1") (pinfunction "1_1") (pintype "passive"))
    )
    (net (code "48") (name "RST_NVM") (class "Default")
      (node (ref "IC1") (pin "18") (pinfunction "~{OBD_TX_LED}/~{RST_NVM}_18") (pintype "bidirectional"))
      (node (ref "R5") (pin "2") (pinfunction "2_2") (pintype "passive"))
    )
    (net (code "49") (name "RX-I") (class "Default")
      (node (ref "H1") (pin "2") (pinfunction "2_2") (pintype "bidirectional"))
      (node (ref "IC1") (pin "13") (pinfunction "UART_RX_13") (pintype "input"))
    )
    (net (code "50") (name "RX-STAT") (class "Default")
      (node (ref "IC1") (pin "21") (pinfunction "~{UART_RX_LED}_21") (pintype "output"))
      (node (ref "R35") (pin "1") (pinfunction "1_1") (pintype "passive"))
    )
    (net (code "51") (name "TX-O") (class "Default")
      (node (ref "H1") (pin "4") (pinfunction "4_4") (pintype "bidirectional"))
      (node (ref "IC1") (pin "14") (pinfunction "UART_TX_14") (pintype "output"))
      (node (ref "R25") (pin "2") (pinfunction "2_2") (pintype "passive"))
    )
    (net (code "52") (name "TX-STAT") (class "Default")
      (node (ref "IC1") (pin "20") (pinfunction "~{UART_TX_LED}_20") (pintype "output"))
      (node (ref "R37") (pin "2") (pinfunction "2_2") (pintype "passive"))
    )
    (net (code "53") (name "VBAT") (class "Default")
      (node (ref "C14") (pin "1") (pinfunction "1_1") (pintype "passive"))
      (node (ref "D1") (pin "C") (pinfunction "C_C") (pintype "passive"))
      (node (ref "IC3") (pin "3") (pinfunction "VCC_3") (pintype "power_in"))
      (node (ref "R10") (pin "1") (pinfunction "1_1") (pintype "passive"))
      (node (ref "R11") (pin "1") (pinfunction "1_1") (pintype "passive"))
      (node (ref "R8") (pin "1") (pinfunction "1_1") (pintype "passive"))
      (node (ref "U2") (pin "3") (pinfunction "IN_3") (pintype "input"))
    )
    (net (code "54") (name "VBATT_RAW") (class "Default")
      (node (ref "D1") (pin "A") (pinfunction "A_A") (pintype "passive"))
      (node (ref "H3") (pin "1") (pinfunction "1_1") (pintype "bidirectional"))
      (node (ref "J1") (pin "16") (pinfunction "16_16") (pintype "passive"))
      (node (ref "R3") (pin "2") (pinfunction "2_2") (pintype "passive"))
    )
    (net (code "55") (name "VCC") (class "Default")
      (node (ref "C10") (pin "1") (pinfunction "1_1") (pintype "passive"))
      (node (ref "C17") (pin "1") (pinfunction "1_1") (pintype "passive"))
      (node (ref "C9") (pin "A") (pinfunction "+_A") (pintype "passive"))
      (node (ref "Q7") (pin "2") (pinfunction "S_2") (pintype "passive"))
      (node (ref "R2") (pin "2") (pinfunction "2_2") (pintype "passive"))
      (node (ref "R20") (pin "1") (pinfunction "1_1") (pintype "passive"))
      (node (ref "R24") (pin "1") (pinfunction "1_1") (pintype "passive"))
      (node (ref "U2") (pin "4") (pinfunction "OUT_4") (pintype "output"))
      (node (ref "U3") (pin "1") (pinfunction "IN_1") (pintype "input"))
      (node (ref "U3") (pin "3") (pinfunction "EN_3") (pintype "input"))
    )
    (net (code "56") (name "unconnected-(H1-Pad6)") (class "Default")
      (node (ref "H1") (pin "6") (pinfunction "6_6") (pintype "bidirectional"))
    )
    (net (code "57") (name "unconnected-(H1-Pad7)") (class "Default")
      (node (ref "H1") (pin "7") (pinfunction "7_7") (pintype "bidirectional"))
    )
    (net (code "58") (name "unconnected-(H1-Pad8)") (class "Default")
      (node (ref "H1") (pin "8") (pinfunction "8_8") (pintype "bidirectional"))
    )
    (net (code "59") (name "unconnected-(H1-Pad9)") (class "Default")
      (node (ref "H1") (pin "9") (pinfunction "9_9") (pintype "bidirectional"))
    )
    (net (code "60") (name "unconnected-(H1-Pad11)") (class "Default")
      (node (ref "H1") (pin "11") (pinfunction "11_11") (pintype "bidirectional"))
    )
    (net (code "61") (name "unconnected-(H1-Pad14)") (class "Default")
      (node (ref "H1") (pin "14") (pinfunction "14_14") (pintype "bidirectional"))
    )
    (net (code "62") (name "unconnected-(IC4-VREF-Pad5)") (class "Default")
      (node (ref "IC4") (pin "5") (pinfunction "VREF_5") (pintype "output"))
    )
    (net (code "63") (name "unconnected-(J1-Pad1)") (class "Default")
      (node (ref "J1") (pin "1") (pinfunction "1_1") (pintype "passive"))
    )
    (net (code "64") (name "unconnected-(J1-Pad3)") (class "Default")
      (node (ref "J1") (pin "3") (pinfunction "3_3") (pintype "passive"))
    )
    (net (code "65") (name "unconnected-(J1-Pad8)") (class "Default")
      (node (ref "J1") (pin "8") (pinfunction "8_8") (pintype "passive"))
    )
    (net (code "66") (name "unconnected-(J1-Pad9)") (class "Default")
      (node (ref "J1") (pin "9") (pinfunction "9_9") (pintype "passive"))
    )
    (net (code "67") (name "unconnected-(J1-Pad11)") (class "Default")
      (node (ref "J1") (pin "11") (pinfunction "11_11") (pintype "passive"))
    )
    (net (code "68") (name "unconnected-(J1-Pad12)") (class "Default")
      (node (ref "J1") (pin "12") (pinfunction "12_12") (pintype "passive"))
    )
    (net (code "69") (name "unconnected-(J1-Pad13)") (class "Default")
      (node (ref "J1") (pin "13") (pinfunction "13_13") (pintype "passive"))
    )
    (net (code "70") (name "unconnected-(U1-BP-Pad4)") (class "Default")
      (node (ref "U1") (pin "4") (pinfunction "BP_4") (pintype "input"))
    )
    (net (code "71") (name "~{ISO_K_TX}") (class "Default")
      (node (ref "IC1") (pin "22") (pinfunction "~{ISO_K_TX}_22") (pintype "output"))
      (node (ref "R13") (pin "2") (pinfunction "2_2") (pintype "passive"))
    )
    (net (code "72") (name "~{ISO_L_TX}") (class "Default")
      (node (ref "IC1") (pin "23") (pinfunction "~{ISO_L_TX}_23") (pintype "output"))
      (node (ref "R7") (pin "2") (pinfunction "2_2") (pintype "passive"))
    )
    (net (code "73") (name "~{ISO_RX}") (class "Default")
      (node (ref "IC1") (pin "8") (pinfunction "~{ISO_RX}_8") (pintype "input"))
      (node (ref "IC3") (pin "2") (pinfunction "OUT_2") (pintype "output"))
      (node (ref "R9") (pin "1") (pinfunction "1_1") (pintype "passive"))
    )
    (net (code "74") (name "~{OBD_RX_STATUS}{slash}PGC") (class "Default")
      (node (ref "IC1") (pin "19") (pinfunction "~{OBD_RX_LED}/~{INT}_19") (pintype "output"))
      (node (ref "R4") (pin "1") (pinfunction "1_1") (pintype "passive"))
    )
    (net (code "75") (name "~{PWR_SAVE}") (class "Default")
      (node (ref "IC1") (pin "15") (pinfunction "PWR_CTRL_15") (pintype "output"))
    )
    (net (code "76") (name "~{VPW_RX}") (class "Default")
      (node (ref "IC1") (pin "1") (pinfunction "~{VPW_RX}_1") (pintype "input"))
      (node (ref "IC3") (pin "14") (pinfunction "OUT_14") (pintype "output"))
      (node (ref "R18") (pin "1") (pinfunction "1_1") (pintype "passive"))
    )
  )
)
